# 11_-_MAIN_CLOCKS.net
KiCad netlist of a schematic drawn in Altium Designer
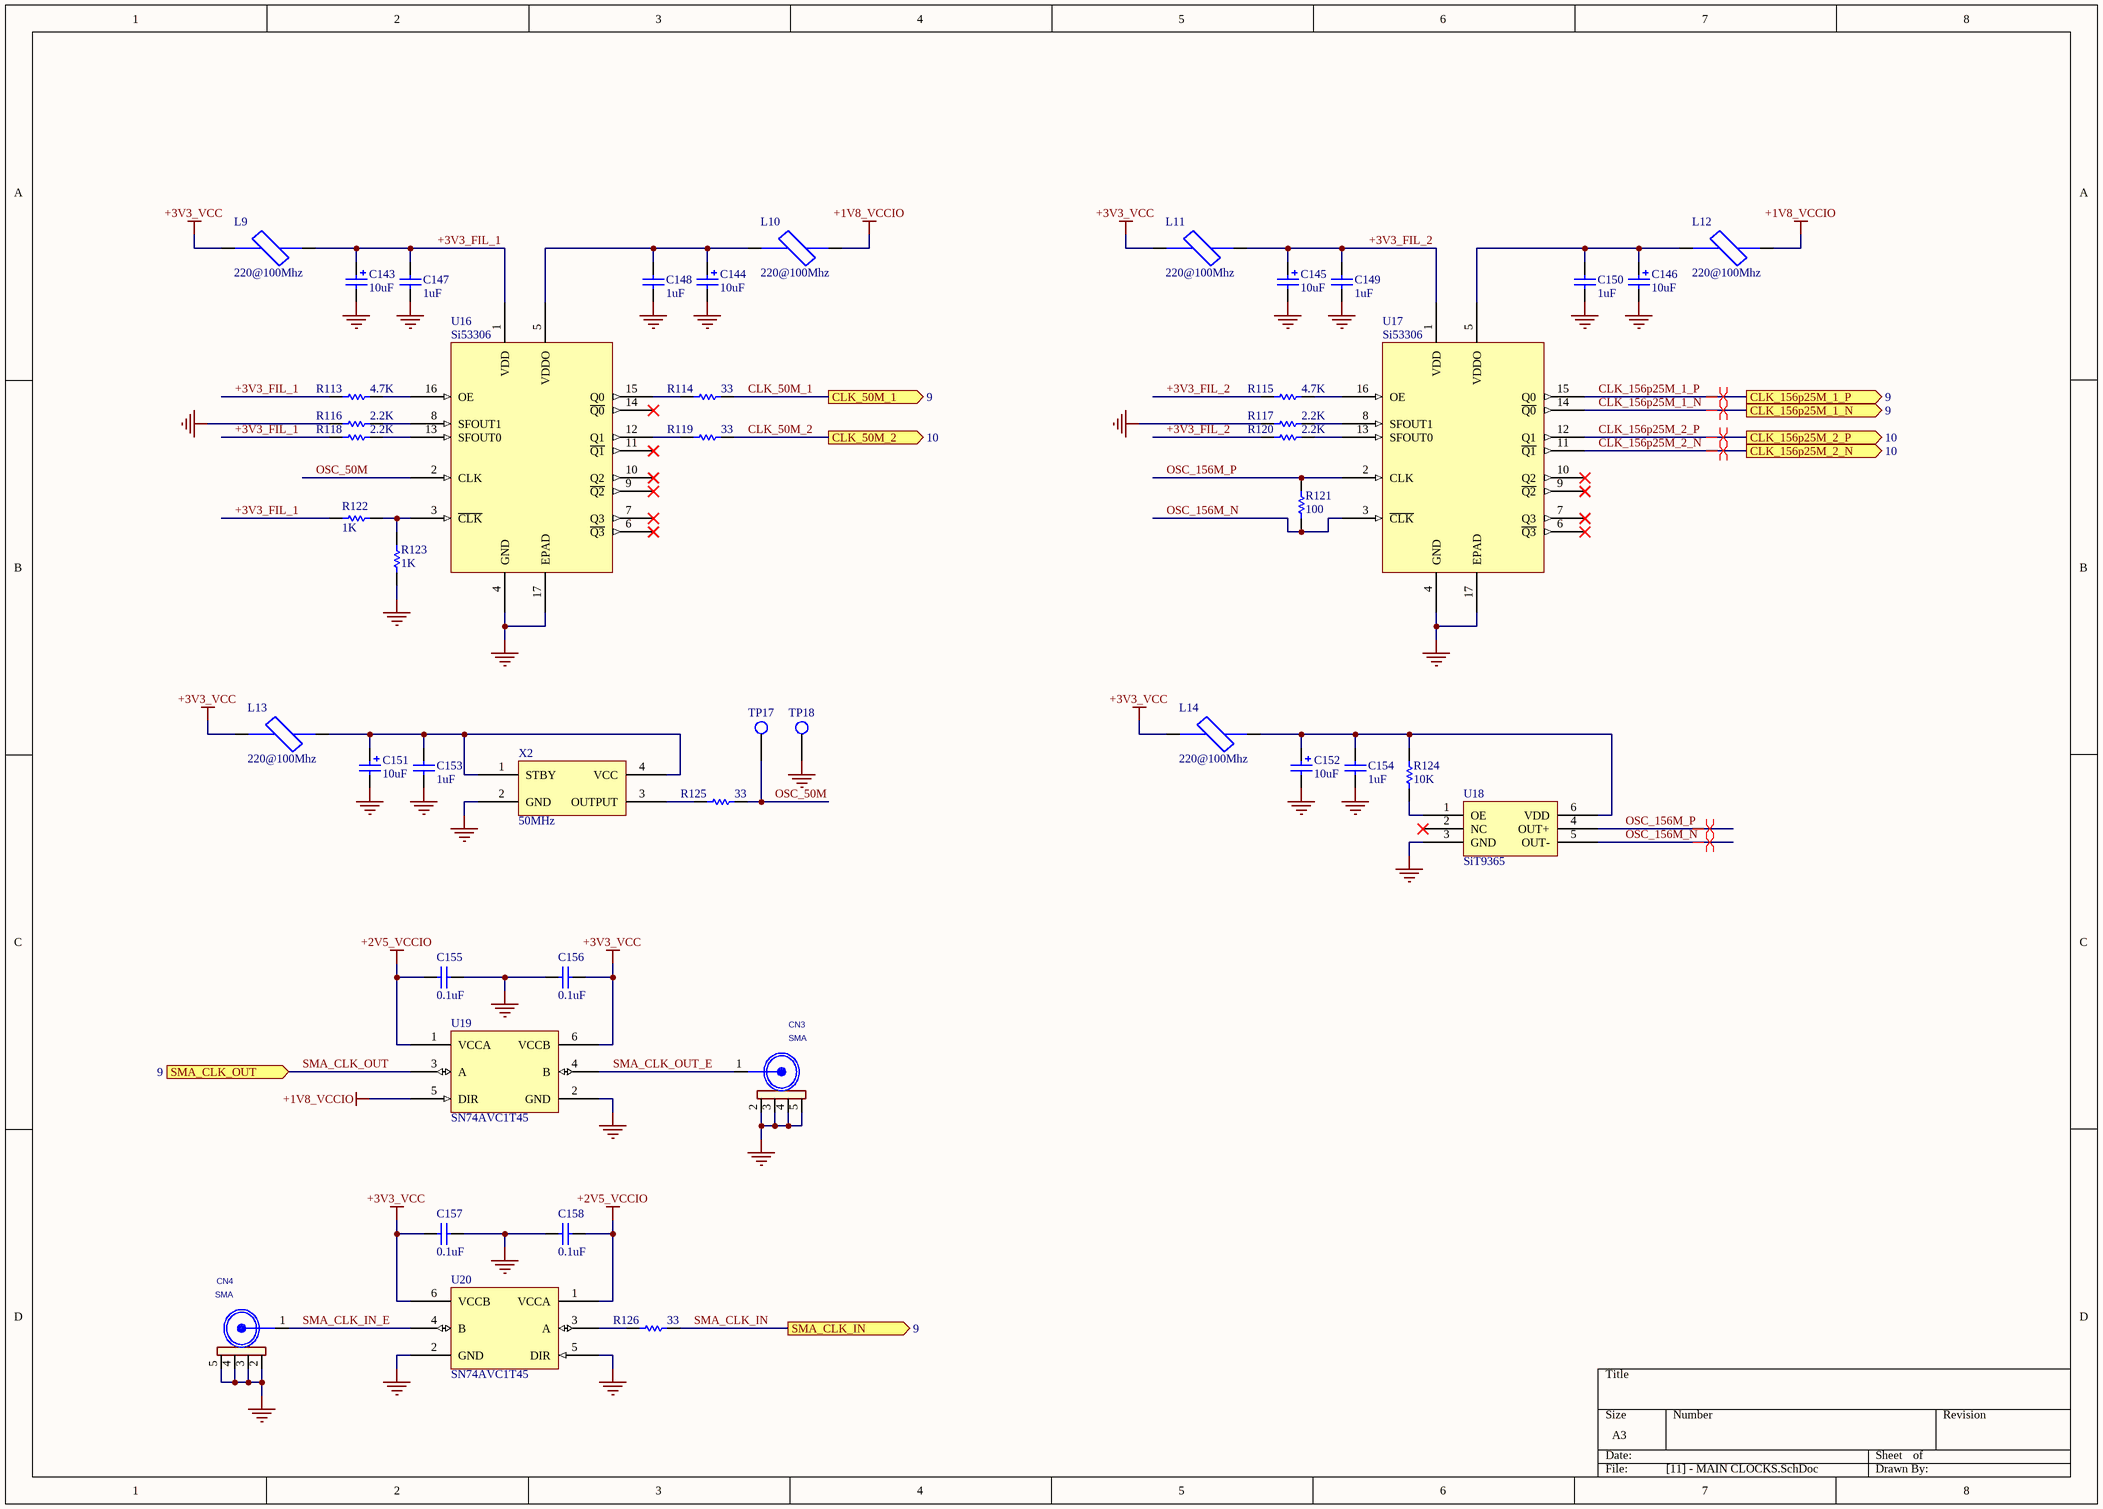
[diagram p0: [11] - MAIN CLOCKS.SchDoc]

(export (version "E")
  (design (tool "Eeschema 10.0.6"))
  (components
    (comp (ref "C143")
      (value "10uF")
      (footprint "TANT_B")
      (description "Tantalum Polarized Capacitor")
      (libsource (lib "Passive Components") (part "Cap Tant"))
    )
    (comp (ref "C144")
      (value "10uF")
      (footprint "TANT_B")
      (description "Tantalum Polarized Capacitor")
      (libsource (lib "Passive Components") (part "Cap Tant"))
    )
    (comp (ref "C145")
      (value "10uF")
      (footprint "TANT_B")
      (description "Tantalum Polarized Capacitor")
      (libsource (lib "Passive Components") (part "Cap Tant"))
    )
    (comp (ref "C146")
      (value "10uF")
      (footprint "TANT_B")
      (description "Tantalum Polarized Capacitor")
      (libsource (lib "Passive Components") (part "Cap Tant"))
    )
    (comp (ref "C147")
      (value "1uF")
      (footprint "0402_C")
      (description "Non-Pol SMD Capacitor")
      (libsource (lib "Passive Components") (part "Cap SMD"))
    )
    (comp (ref "C148")
      (value "1uF")
      (footprint "0402_C")
      (description "Non-Pol SMD Capacitor")
      (libsource (lib "Passive Components") (part "Cap SMD"))
    )
    (comp (ref "C149")
      (value "1uF")
      (footprint "0402_C")
      (description "Non-Pol SMD Capacitor")
      (libsource (lib "Passive Components") (part "Cap SMD"))
    )
    (comp (ref "C150")
      (value "1uF")
      (footprint "0402_C")
      (description "Non-Pol SMD Capacitor")
      (libsource (lib "Passive Components") (part "Cap SMD"))
    )
    (comp (ref "C151")
      (value "10uF")
      (footprint "TANT_B")
      (description "Tantalum Polarized Capacitor")
      (libsource (lib "Passive Components") (part "Cap Tant"))
    )
    (comp (ref "C152")
      (value "10uF")
      (footprint "TANT_B")
      (description "Tantalum Polarized Capacitor")
      (libsource (lib "Passive Components") (part "Cap Tant"))
    )
    (comp (ref "C153")
      (value "1uF")
      (footprint "0402_C")
      (description "Non-Pol SMD Capacitor")
      (libsource (lib "Passive Components") (part "Cap SMD"))
    )
    (comp (ref "C154")
      (value "1uF")
      (footprint "0402_C")
      (description "Non-Pol SMD Capacitor")
      (libsource (lib "Passive Components") (part "Cap SMD"))
    )
    (comp (ref "C155")
      (value "0.1uF")
      (footprint "0402_C")
      (description "Non-Pol SMD Capacitor")
      (libsource (lib "Passive Components") (part "Cap SMD"))
    )
    (comp (ref "C156")
      (value "0.1uF")
      (footprint "0402_C")
      (description "Non-Pol SMD Capacitor")
      (libsource (lib "Passive Components") (part "Cap SMD"))
    )
    (comp (ref "C157")
      (value "0.1uF")
      (footprint "0402_C")
      (description "Non-Pol SMD Capacitor")
      (libsource (lib "Passive Components") (part "Cap SMD"))
    )
    (comp (ref "C158")
      (value "0.1uF")
      (footprint "0402_C")
      (description "Non-Pol SMD Capacitor")
      (libsource (lib "Passive Components") (part "Cap SMD"))
    )
    (comp (ref "CN3")
      (value "SMA")
      (footprint "SMA_STRAIGHT")
      (description "CONN -  SMA VERTICAL GOLD PLATED SMT CENTER CONDUCTOR")
      (libsource (lib "Connectors") (part "SMA Straight"))
    )
    (comp (ref "CN4")
      (value "SMA")
      (footprint "SMA_STRAIGHT")
      (description "CONN -  SMA VERTICAL GOLD PLATED SMT CENTER CONDUCTOR")
      (libsource (lib "") (part "SMA Straight_1"))
    )
    (comp (ref "L9")
      (value "220@100Mhz")
      (footprint "0805_L")
      (description "Ferrite Bead")
      (libsource (lib "Passive Components") (part "Ferrite Bead"))
    )
    (comp (ref "L10")
      (value "220@100Mhz")
      (footprint "0805_L")
      (description "Ferrite Bead")
      (libsource (lib "Passive Components") (part "Ferrite Bead"))
    )
    (comp (ref "L11")
      (value "220@100Mhz")
      (footprint "0805_L")
      (description "Ferrite Bead")
      (libsource (lib "Passive Components") (part "Ferrite Bead"))
    )
    (comp (ref "L12")
      (value "220@100Mhz")
      (footprint "0805_L")
      (description "Ferrite Bead")
      (libsource (lib "Passive Components") (part "Ferrite Bead"))
    )
    (comp (ref "L13")
      (value "220@100Mhz")
      (footprint "0805_L")
      (description "Ferrite Bead")
      (libsource (lib "Passive Components") (part "Ferrite Bead"))
    )
    (comp (ref "L14")
      (value "220@100Mhz")
      (footprint "0805_L")
      (description "Ferrite Bead")
      (libsource (lib "Passive Components") (part "Ferrite Bead"))
    )
    (comp (ref "R113")
      (value "4.7K")
      (footprint "0402_R")
      (description "SMD Resistor")
      (fields (field (name "TOLERANCE") "5%"))
      (libsource (lib "Passive Components") (part "Res SMD"))
    )
    (comp (ref "R114")
      (value "33")
      (footprint "0402_R")
      (description "SMD Resistor")
      (fields (field (name "TOLERANCE") "5%"))
      (libsource (lib "Passive Components") (part "Res SMD"))
    )
    (comp (ref "R115")
      (value "4.7K")
      (footprint "0402_R")
      (description "SMD Resistor")
      (fields (field (name "TOLERANCE") "5%"))
      (libsource (lib "Passive Components") (part "Res SMD"))
    )
    (comp (ref "R116")
      (value "2.2K")
      (footprint "0402_R")
      (description "SMD Resistor")
      (fields (field (name "TOLERANCE") "5%"))
      (libsource (lib "Passive Components") (part "Res SMD"))
    )
    (comp (ref "R117")
      (value "2.2K")
      (footprint "0402_R")
      (description "SMD Resistor")
      (fields (field (name "TOLERANCE") "5%"))
      (libsource (lib "Passive Components") (part "Res SMD"))
    )
    (comp (ref "R118")
      (value "2.2K")
      (footprint "0402_R")
      (description "SMD Resistor")
      (fields (field (name "TOLERANCE") "5%"))
      (libsource (lib "Passive Components") (part "Res SMD"))
    )
    (comp (ref "R119")
      (value "33")
      (footprint "0402_R")
      (description "SMD Resistor")
      (fields (field (name "TOLERANCE") "5%"))
      (libsource (lib "Passive Components") (part "Res SMD"))
    )
    (comp (ref "R120")
      (value "2.2K")
      (footprint "0402_R")
      (description "SMD Resistor")
      (fields (field (name "TOLERANCE") "5%"))
      (libsource (lib "Passive Components") (part "Res SMD"))
    )
    (comp (ref "R121")
      (value "100")
      (footprint "0402_R")
      (description "SMD Resistor")
      (fields (field (name "TOLERANCE") "5%"))
      (libsource (lib "Passive Components") (part "Res SMD"))
    )
    (comp (ref "R122")
      (value "1K")
      (footprint "0402_R")
      (description "SMD Resistor")
      (fields (field (name "TOLERANCE") "5%"))
      (libsource (lib "Passive Components") (part "Res SMD"))
    )
    (comp (ref "R123")
      (value "1K")
      (footprint "0402_R")
      (description "SMD Resistor")
      (fields (field (name "TOLERANCE") "5%"))
      (libsource (lib "Passive Components") (part "Res SMD"))
    )
    (comp (ref "R124")
      (value "10K")
      (footprint "0402_R")
      (description "SMD Resistor")
      (fields (field (name "TOLERANCE") "5%"))
      (libsource (lib "Passive Components") (part "Res SMD"))
    )
    (comp (ref "R125")
      (value "33")
      (footprint "0402_R")
      (description "SMD Resistor")
      (fields (field (name "TOLERANCE") "5%"))
      (libsource (lib "Passive Components") (part "Res SMD"))
    )
    (comp (ref "R126")
      (value "33")
      (footprint "0402_R")
      (description "SMD Resistor")
      (fields (field (name "TOLERANCE") "5%"))
      (libsource (lib "Passive Components") (part "Res SMD"))
    )
    (comp (ref "TP17")
      (value "Test Point")
      (footprint "PIN_1mm")
      (description "Test Point Footprint")
      (libsource (lib "Passive Components") (part "Test Point"))
    )
    (comp (ref "TP18")
      (value "Test Point")
      (footprint "PIN_1mm")
      (description "Test Point Footprint")
      (libsource (lib "Passive Components") (part "Test Point"))
    )
    (comp (ref "U16")
      (value "Si53306")
      (description "Ultra-Low Additive Jitter Fanout Clock Buffer")
      (fields (field (name "MANUFACTURER PART NUM") "Si53306-B-GM"))
      (libsource (lib "Project_schlib") (part "Si53306"))
    )
    (comp (ref "U17")
      (value "Si53306")
      (description "Ultra-Low Additive Jitter Fanout Clock Buffer")
      (fields (field (name "MANUFACTURER PART NUM") "Si53306-B-GM"))
      (libsource (lib "Project_schlib") (part "Si53306"))
    )
    (comp (ref "U18")
      (value "SiT9365")
      (description "Standard Frequency Ultra-low Jitter Differential Oscillator")
      (fields (field (name "MANUFACTURER PART NUM") "SIT9365AC-2B2-33E156.250000G"))
      (libsource (lib "Project_schlib") (part "SiT9365"))
    )
    (comp (ref "U19")
      (value "SN74AVC1T45")
      (description "Single-Bit Dual-Supply Bus Transceiver With Configurable Voltage Translation")
      (libsource (lib "") (part "SN74AVC1T45_1"))
    )
    (comp (ref "U20")
      (value "SN74AVC1T45")
      (description "Single-Bit Dual-Supply Bus Transceiver With Configurable Voltage Translation")
      (libsource (lib "Project_schlib") (part "SN74AVC1T45"))
    )
    (comp (ref "X2")
      (value "50MHz")
      (footprint "OSC_3.2x2.5")
      (description "Crystal Oscillator")
      (libsource (lib "Common Components") (part "XTAL OSC"))
    )
  )
  (nets
    (net (code "1") (name "+1V8_VCCIO") (class "Default")
      (node (ref "L10") (pin "2") (pinfunction "2_2") (pintype "passive"))
      (node (ref "L12") (pin "2") (pinfunction "2_2") (pintype "passive"))
      (node (ref "U19") (pin "5") (pinfunction "DIR_5") (pintype "input"))
    )
    (net (code "2") (name "+2V5_VCCIO") (class "Default")
      (node (ref "C155") (pin "2") (pinfunction "2_2") (pintype "passive"))
      (node (ref "C158") (pin "1") (pinfunction "1_1") (pintype "passive"))
      (node (ref "U19") (pin "1") (pinfunction "VCCA_1") (pintype "power_in"))
      (node (ref "U20") (pin "1") (pinfunction "VCCA_1") (pintype "power_in"))
    )
    (net (code "3") (name "+3V3_VCC") (class "Default")
      (node (ref "C156") (pin "1") (pinfunction "1_1") (pintype "passive"))
      (node (ref "C157") (pin "2") (pinfunction "2_2") (pintype "passive"))
      (node (ref "L11") (pin "1") (pinfunction "1_1") (pintype "passive"))
      (node (ref "L13") (pin "1") (pinfunction "1_1") (pintype "passive"))
      (node (ref "L14") (pin "1") (pinfunction "1_1") (pintype "passive"))
      (node (ref "L9") (pin "1") (pinfunction "1_1") (pintype "passive"))
      (node (ref "U19") (pin "6") (pinfunction "VCCB_6") (pintype "power_in"))
      (node (ref "U20") (pin "6") (pinfunction "VCCB_6") (pintype "power_in"))
    )
    (net (code "4") (name "/+3V3_FIL_1") (class "Default")
      (node (ref "C143") (pin "1") (pinfunction "1_1") (pintype "passive"))
      (node (ref "C147") (pin "2") (pinfunction "2_2") (pintype "passive"))
      (node (ref "L9") (pin "2") (pinfunction "2_2") (pintype "passive"))
      (node (ref "R113") (pin "1") (pinfunction "1_1") (pintype "passive"))
      (node (ref "R118") (pin "1") (pinfunction "1_1") (pintype "passive"))
      (node (ref "R122") (pin "1") (pinfunction "1_1") (pintype "passive"))
      (node (ref "U16") (pin "1") (pinfunction "VDD_1") (pintype "power_in"))
    )
    (net (code "5") (name "/+3V3_FIL_2") (class "Default")
      (node (ref "C145") (pin "1") (pinfunction "1_1") (pintype "passive"))
      (node (ref "C149") (pin "2") (pinfunction "2_2") (pintype "passive"))
      (node (ref "L11") (pin "2") (pinfunction "2_2") (pintype "passive"))
      (node (ref "R115") (pin "1") (pinfunction "1_1") (pintype "passive"))
      (node (ref "R120") (pin "1") (pinfunction "1_1") (pintype "passive"))
      (node (ref "U17") (pin "1") (pinfunction "VDD_1") (pintype "power_in"))
    )
    (net (code "6") (name "/CLK_50M_1") (class "Default")
      (node (ref "R114") (pin "2") (pinfunction "2_2") (pintype "passive"))
    )
    (net (code "7") (name "/CLK_50M_2") (class "Default")
      (node (ref "R119") (pin "2") (pinfunction "2_2") (pintype "passive"))
    )
    (net (code "8") (name "/CLK_156p25M_1_N") (class "Default")
      (node (ref "U17") (pin "14") (pinfunction "~{Q0}_14") (pintype "output"))
    )
    (net (code "9") (name "/CLK_156p25M_1_P") (class "Default")
      (node (ref "U17") (pin "15") (pinfunction "Q0_15") (pintype "output"))
    )
    (net (code "10") (name "/CLK_156p25M_2_N") (class "Default")
      (node (ref "U17") (pin "11") (pinfunction "~{Q1}_11") (pintype "output"))
    )
    (net (code "11") (name "/CLK_156p25M_2_P") (class "Default")
      (node (ref "U17") (pin "12") (pinfunction "Q1_12") (pintype "output"))
    )
    (net (code "12") (name "/OSC_50M") (class "Default")
      (node (ref "R125") (pin "2") (pinfunction "2_2") (pintype "passive"))
      (node (ref "TP17") (pin "1") (pinfunction "1_1") (pintype "passive"))
      (node (ref "U16") (pin "2") (pinfunction "CLK_2") (pintype "input"))
    )
    (net (code "13") (name "/OSC_156M_N") (class "Default")
      (node (ref "R121") (pin "1") (pinfunction "1_1") (pintype "passive"))
      (node (ref "U17") (pin "3") (pinfunction "~{CLK}_3") (pintype "input"))
      (node (ref "U18") (pin "5") (pinfunction "OUT-_5") (pintype "passive"))
    )
    (net (code "14") (name "/OSC_156M_P") (class "Default")
      (node (ref "R121") (pin "2") (pinfunction "2_2") (pintype "passive"))
      (node (ref "U17") (pin "2") (pinfunction "CLK_2") (pintype "input"))
      (node (ref "U18") (pin "4") (pinfunction "OUT+_4") (pintype "passive"))
    )
    (net (code "15") (name "/SMA_CLK_IN") (class "Default")
      (node (ref "R126") (pin "2") (pinfunction "2_2") (pintype "passive"))
    )
    (net (code "16") (name "/SMA_CLK_IN_E") (class "Default")
      (node (ref "CN4") (pin "1") (pinfunction "1_1") (pintype "passive"))
      (node (ref "U20") (pin "4") (pinfunction "B_4") (pintype "bidirectional"))
    )
    (net (code "17") (name "/SMA_CLK_OUT") (class "Default")
      (node (ref "U19") (pin "3") (pinfunction "A_3") (pintype "bidirectional"))
    )
    (net (code "18") (name "/SMA_CLK_OUT_E") (class "Default")
      (node (ref "CN3") (pin "1") (pinfunction "1_1") (pintype "passive"))
      (node (ref "U19") (pin "4") (pinfunction "B_4") (pintype "bidirectional"))
    )
    (net (code "19") (name "GND") (class "Default")
      (node (ref "C143") (pin "2") (pinfunction "2_2") (pintype "passive"))
      (node (ref "C144") (pin "2") (pinfunction "2_2") (pintype "passive"))
      (node (ref "C145") (pin "2") (pinfunction "2_2") (pintype "passive"))
      (node (ref "C146") (pin "2") (pinfunction "2_2") (pintype "passive"))
      (node (ref "C147") (pin "1") (pinfunction "1_1") (pintype "passive"))
      (node (ref "C148") (pin "1") (pinfunction "1_1") (pintype "passive"))
      (node (ref "C149") (pin "1") (pinfunction "1_1") (pintype "passive"))
      (node (ref "C150") (pin "1") (pinfunction "1_1") (pintype "passive"))
      (node (ref "C151") (pin "2") (pinfunction "2_2") (pintype "passive"))
      (node (ref "C152") (pin "2") (pinfunction "2_2") (pintype "passive"))
      (node (ref "C153") (pin "1") (pinfunction "1_1") (pintype "passive"))
      (node (ref "C154") (pin "1") (pinfunction "1_1") (pintype "passive"))
      (node (ref "C155") (pin "1") (pinfunction "1_1") (pintype "passive"))
      (node (ref "C156") (pin "2") (pinfunction "2_2") (pintype "passive"))
      (node (ref "C157") (pin "1") (pinfunction "1_1") (pintype "passive"))
      (node (ref "C158") (pin "2") (pinfunction "2_2") (pintype "passive"))
      (node (ref "CN3") (pin "2") (pinfunction "2_2") (pintype "power_in"))
      (node (ref "CN3") (pin "3") (pinfunction "3_3") (pintype "power_in"))
      (node (ref "CN3") (pin "4") (pinfunction "4_4") (pintype "power_in"))
      (node (ref "CN3") (pin "5") (pinfunction "5_5") (pintype "power_in"))
      (node (ref "CN4") (pin "2") (pinfunction "2_2") (pintype "power_in"))
      (node (ref "CN4") (pin "3") (pinfunction "3_3") (pintype "power_in"))
      (node (ref "CN4") (pin "4") (pinfunction "4_4") (pintype "power_in"))
      (node (ref "CN4") (pin "5") (pinfunction "5_5") (pintype "power_in"))
      (node (ref "R116") (pin "1") (pinfunction "1_1") (pintype "passive"))
      (node (ref "R117") (pin "1") (pinfunction "1_1") (pintype "passive"))
      (node (ref "R123") (pin "1") (pinfunction "1_1") (pintype "passive"))
      (node (ref "TP18") (pin "1") (pinfunction "1_1") (pintype "passive"))
      (node (ref "U16") (pin "17") (pinfunction "EPAD_17") (pintype "power_in"))
      (node (ref "U16") (pin "4") (pinfunction "GND_4") (pintype "power_in"))
      (node (ref "U17") (pin "17") (pinfunction "EPAD_17") (pintype "power_in"))
      (node (ref "U17") (pin "4") (pinfunction "GND_4") (pintype "power_in"))
      (node (ref "U18") (pin "3") (pinfunction "GND_3") (pintype "passive"))
      (node (ref "U19") (pin "2") (pinfunction "GND_2") (pintype "power_in"))
      (node (ref "U20") (pin "2") (pinfunction "GND_2") (pintype "power_in"))
      (node (ref "U20") (pin "5") (pinfunction "DIR_5") (pintype "input"))
      (node (ref "X2") (pin "2") (pinfunction "GND_2") (pintype "passive"))
    )
    (net (code "20") (name "Net-(U16-OE)") (class "Default")
      (node (ref "R113") (pin "2") (pinfunction "2_2") (pintype "passive"))
      (node (ref "U16") (pin "16") (pinfunction "OE_16") (pintype "input"))
    )
    (net (code "21") (name "Net-(U16-Q0)") (class "Default")
      (node (ref "R114") (pin "1") (pinfunction "1_1") (pintype "passive"))
      (node (ref "U16") (pin "15") (pinfunction "Q0_15") (pintype "output"))
    )
    (net (code "22") (name "Net-(U16-Q1)") (class "Default")
      (node (ref "R119") (pin "1") (pinfunction "1_1") (pintype "passive"))
      (node (ref "U16") (pin "12") (pinfunction "Q1_12") (pintype "output"))
    )
    (net (code "23") (name "Net-(U16-SFOUT0)") (class "Default")
      (node (ref "R118") (pin "2") (pinfunction "2_2") (pintype "passive"))
      (node (ref "U16") (pin "13") (pinfunction "SFOUT0_13") (pintype "input"))
    )
    (net (code "24") (name "Net-(U16-SFOUT1)") (class "Default")
      (node (ref "R116") (pin "2") (pinfunction "2_2") (pintype "passive"))
      (node (ref "U16") (pin "8") (pinfunction "SFOUT1_8") (pintype "input"))
    )
    (net (code "25") (name "Net-(U16-VDDO)") (class "Default")
      (node (ref "C144") (pin "1") (pinfunction "1_1") (pintype "passive"))
      (node (ref "C148") (pin "2") (pinfunction "2_2") (pintype "passive"))
      (node (ref "L10") (pin "1") (pinfunction "1_1") (pintype "passive"))
      (node (ref "U16") (pin "5") (pinfunction "VDDO_5") (pintype "power_in"))
    )
    (net (code "26") (name "Net-(U16-~{CLK})") (class "Default")
      (node (ref "R122") (pin "2") (pinfunction "2_2") (pintype "passive"))
      (node (ref "R123") (pin "2") (pinfunction "2_2") (pintype "passive"))
      (node (ref "U16") (pin "3") (pinfunction "~{CLK}_3") (pintype "input"))
    )
    (net (code "27") (name "Net-(U17-OE)") (class "Default")
      (node (ref "R115") (pin "2") (pinfunction "2_2") (pintype "passive"))
      (node (ref "U17") (pin "16") (pinfunction "OE_16") (pintype "input"))
    )
    (net (code "28") (name "Net-(U17-SFOUT0)") (class "Default")
      (node (ref "R120") (pin "2") (pinfunction "2_2") (pintype "passive"))
      (node (ref "U17") (pin "13") (pinfunction "SFOUT0_13") (pintype "input"))
    )
    (net (code "29") (name "Net-(U17-SFOUT1)") (class "Default")
      (node (ref "R117") (pin "2") (pinfunction "2_2") (pintype "passive"))
      (node (ref "U17") (pin "8") (pinfunction "SFOUT1_8") (pintype "input"))
    )
    (net (code "30") (name "Net-(U17-VDDO)") (class "Default")
      (node (ref "C146") (pin "1") (pinfunction "1_1") (pintype "passive"))
      (node (ref "C150") (pin "2") (pinfunction "2_2") (pintype "passive"))
      (node (ref "L12") (pin "1") (pinfunction "1_1") (pintype "passive"))
      (node (ref "U17") (pin "5") (pinfunction "VDDO_5") (pintype "power_in"))
    )
    (net (code "31") (name "Net-(U18-OE)") (class "Default")
      (node (ref "R124") (pin "1") (pinfunction "1_1") (pintype "passive"))
      (node (ref "U18") (pin "1") (pinfunction "OE_1") (pintype "passive"))
    )
    (net (code "32") (name "Net-(U18-VDD)") (class "Default")
      (node (ref "C152") (pin "1") (pinfunction "1_1") (pintype "passive"))
      (node (ref "C154") (pin "2") (pinfunction "2_2") (pintype "passive"))
      (node (ref "L14") (pin "2") (pinfunction "2_2") (pintype "passive"))
      (node (ref "R124") (pin "2") (pinfunction "2_2") (pintype "passive"))
      (node (ref "U18") (pin "6") (pinfunction "VDD_6") (pintype "passive"))
    )
    (net (code "33") (name "Net-(U20-A)") (class "Default")
      (node (ref "R126") (pin "1") (pinfunction "1_1") (pintype "passive"))
      (node (ref "U20") (pin "3") (pinfunction "A_3") (pintype "bidirectional"))
    )
    (net (code "34") (name "Net-(X2-OUTPUT)") (class "Default")
      (node (ref "R125") (pin "1") (pinfunction "1_1") (pintype "passive"))
      (node (ref "X2") (pin "3") (pinfunction "OUTPUT_3") (pintype "passive"))
    )
    (net (code "35") (name "Net-(X2-STBY)") (class "Default")
      (node (ref "C151") (pin "1") (pinfunction "1_1") (pintype "passive"))
      (node (ref "C153") (pin "2") (pinfunction "2_2") (pintype "passive"))
      (node (ref "L13") (pin "2") (pinfunction "2_2") (pintype "passive"))
      (node (ref "X2") (pin "1") (pinfunction "STBY_1") (pintype "passive"))
      (node (ref "X2") (pin "4") (pinfunction "VCC_4") (pintype "passive"))
    )
    (net (code "36") (name "unconnected-(U16-Q2-Pad10)") (class "Default")
      (node (ref "U16") (pin "10") (pinfunction "Q2_10") (pintype "output+no_connect"))
    )
    (net (code "37") (name "unconnected-(U16-Q3-Pad7)") (class "Default")
      (node (ref "U16") (pin "7") (pinfunction "Q3_7") (pintype "output+no_connect"))
    )
    (net (code "38") (name "unconnected-(U16-~{Q0}-Pad14)") (class "Default")
      (node (ref "U16") (pin "14") (pinfunction "~{Q0}_14") (pintype "output+no_connect"))
    )
    (net (code "39") (name "unconnected-(U16-~{Q1}-Pad11)") (class "Default")
      (node (ref "U16") (pin "11") (pinfunction "~{Q1}_11") (pintype "output+no_connect"))
    )
    (net (code "40") (name "unconnected-(U16-~{Q2}-Pad9)") (class "Default")
      (node (ref "U16") (pin "9") (pinfunction "~{Q2}_9") (pintype "output+no_connect"))
    )
    (net (code "41") (name "unconnected-(U16-~{Q3}-Pad6)") (class "Default")
      (node (ref "U16") (pin "6") (pinfunction "~{Q3}_6") (pintype "output+no_connect"))
    )
    (net (code "42") (name "unconnected-(U17-Q2-Pad10)") (class "Default")
      (node (ref "U17") (pin "10") (pinfunction "Q2_10") (pintype "output+no_connect"))
    )
    (net (code "43") (name "unconnected-(U17-Q3-Pad7)") (class "Default")
      (node (ref "U17") (pin "7") (pinfunction "Q3_7") (pintype "output+no_connect"))
    )
    (net (code "44") (name "unconnected-(U17-~{Q2}-Pad9)") (class "Default")
      (node (ref "U17") (pin "9") (pinfunction "~{Q2}_9") (pintype "output+no_connect"))
    )
    (net (code "45") (name "unconnected-(U17-~{Q3}-Pad6)") (class "Default")
      (node (ref "U17") (pin "6") (pinfunction "~{Q3}_6") (pintype "output+no_connect"))
    )
    (net (code "46") (name "unconnected-(U18-NC-Pad2)") (class "Default")
      (node (ref "U18") (pin "2") (pinfunction "NC_2") (pintype "passive+no_connect"))
    )
  )
)
